# mem.net
KiCad netlist of a schematic drawn in Altium Designer
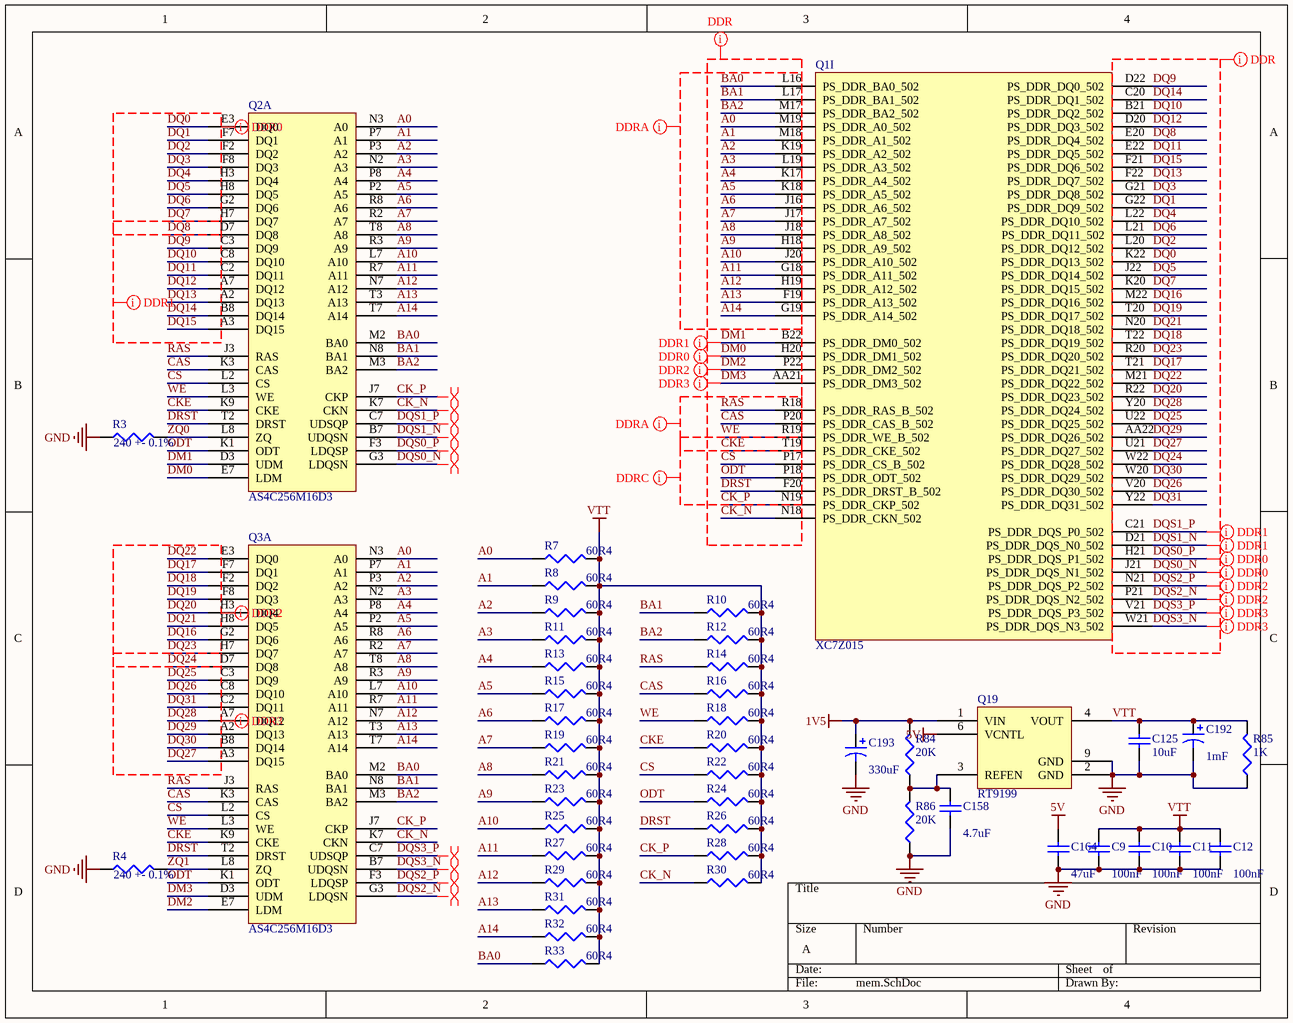
[diagram p0: mem.SchDoc]

(export (version "E")
  (design (tool "Eeschema 10.0.6"))
  (components
    (comp (ref "C9")
      (value "100nF")
      (footprint "CAPC1005X06L")
      (description "Capacitor")
      (fields (field (name "Comment") "Cap") (field (name "PUBLISHER") "Altium Limited"))
      (libsource (lib "Miscellaneous Devices") (part "Cap"))
    )
    (comp (ref "C10")
      (value "100nF")
      (footprint "CAPC1005X06L")
      (description "Capacitor")
      (fields (field (name "Comment") "Cap") (field (name "PUBLISHER") "Altium Limited"))
      (libsource (lib "Miscellaneous Devices") (part "Cap"))
    )
    (comp (ref "C11")
      (value "100nF")
      (footprint "CAPC1005X06L")
      (description "Capacitor")
      (fields (field (name "Comment") "Cap") (field (name "PUBLISHER") "Altium Limited"))
      (libsource (lib "Miscellaneous Devices") (part "Cap"))
    )
    (comp (ref "C12")
      (value "100nF")
      (footprint "CAPC1005X06L")
      (description "Capacitor")
      (fields (field (name "Comment") "Cap") (field (name "PUBLISHER") "Altium Limited"))
      (libsource (lib "Miscellaneous Devices") (part "Cap"))
    )
    (comp (ref "C125")
      (value "10uF")
      (footprint "CAPC1608X90N")
      (description "Capacitor")
      (fields (field (name "Comment") "GRM188R60G106ME47") (field (name "PUBLISHER") "Altium Limited"))
      (libsource (lib "Miscellaneous Devices") (part "Cap"))
    )
    (comp (ref "C158")
      (value "4.7uF")
      (footprint "CAPC1608X90N")
      (description "Capacitor")
      (fields (field (name "Comment") "GRM188R60J475ME19D") (field (name "PUBLISHER") "Altium Limited"))
      (libsource (lib "Miscellaneous Devices") (part "Cap"))
    )
    (comp (ref "C164")
      (value "47uF")
      (footprint "CAPC3225X220N")
      (description "Capacitor")
      (fields (field (name "Comment") "GRM31CR60J476ME19L") (field (name "PUBLISHER") "Altium Limited"))
      (libsource (lib "Miscellaneous Devices") (part "Cap"))
    )
    (comp (ref "C192")
      (value "1mF")
      (footprint "CAP-D/7343-31")
      (description "Polarized Capacitor (Radial)")
      (fields (field (name "Comment") "TR3E108M004C0100") (field (name "PUBLISHER") "Altium Limited"))
      (libsource (lib "Miscellaneous Devices") (part "Cap Pol1"))
    )
    (comp (ref "C193")
      (value "330uF")
      (footprint "CAP-D/7343-31")
      (description "Polarized Capacitor (Radial)")
      (fields (field (name "Comment") "T520D337M006ATE018") (field (name "PUBLISHER") "Altium Limited"))
      (libsource (lib "Miscellaneous Devices") (part "Cap Pol1"))
    )
    (comp (ref "Q1") (value "XC7Z015") (footprint "BGA484x22") (libsource (lib "schlib") (part "XC7Z015")))
    (comp (ref "Q2")
      (value "AS4C256M16D3")
      (footprint "DDR3")
      (libsource (lib "schlib") (part "AS4C256M16D3"))
    )
    (comp (ref "Q3")
      (value "AS4C256M16D3")
      (footprint "DDR3")
      (libsource (lib "schlib") (part "AS4C256M16D3"))
    )
    (comp (ref "Q19")
      (value "RT9199")
      (footprint "SOIC127P600X135_HS-9N")
      (libsource (lib "schlib") (part "RT9199"))
    )
    (comp (ref "R3")
      (value "240 +- 0.1%")
      (footprint "J1-0603")
      (description "Resistor")
      (fields (field (name "Comment") "RG1608P-241-B-T5") (field (name "PUBLISHER") "Altium Limited"))
      (libsource (lib "Miscellaneous Devices") (part "Res3"))
    )
    (comp (ref "R4")
      (value "240 +- 0.1%")
      (footprint "J1-0603")
      (description "Resistor")
      (fields (field (name "Comment") "RG1608P-241-B-T5") (field (name "PUBLISHER") "Altium Limited"))
      (libsource (lib "Miscellaneous Devices") (part "Res3"))
    )
    (comp (ref "R7")
      (value "60R4")
      (footprint "CAPC1005X06L")
      (description "Resistor")
      (fields (field (name "Comment") "RC1005F60R4CS") (field (name "PUBLISHER") "Altium Limited"))
      (libsource (lib "Miscellaneous Devices") (part "Res3"))
    )
    (comp (ref "R8")
      (value "60R4")
      (footprint "CAPC1005X06L")
      (description "Resistor")
      (fields (field (name "Comment") "RC1005F60R4CS") (field (name "PUBLISHER") "Altium Limited"))
      (libsource (lib "Miscellaneous Devices") (part "Res3"))
    )
    (comp (ref "R9")
      (value "60R4")
      (footprint "CAPC1005X06L")
      (description "Resistor")
      (fields (field (name "Comment") "RC1005F60R4CS") (field (name "PUBLISHER") "Altium Limited"))
      (libsource (lib "Miscellaneous Devices") (part "Res3"))
    )
    (comp (ref "R10")
      (value "60R4")
      (footprint "CAPC1005X06L")
      (description "Resistor")
      (fields (field (name "Comment") "RC1005F60R4CS") (field (name "PUBLISHER") "Altium Limited"))
      (libsource (lib "Miscellaneous Devices") (part "Res3"))
    )
    (comp (ref "R11")
      (value "60R4")
      (footprint "CAPC1005X06L")
      (description "Resistor")
      (fields (field (name "Comment") "RC1005F60R4CS") (field (name "PUBLISHER") "Altium Limited"))
      (libsource (lib "Miscellaneous Devices") (part "Res3"))
    )
    (comp (ref "R12")
      (value "60R4")
      (footprint "CAPC1005X06L")
      (description "Resistor")
      (fields (field (name "Comment") "RC1005F60R4CS") (field (name "PUBLISHER") "Altium Limited"))
      (libsource (lib "Miscellaneous Devices") (part "Res3"))
    )
    (comp (ref "R13")
      (value "60R4")
      (footprint "CAPC1005X06L")
      (description "Resistor")
      (fields (field (name "Comment") "RC1005F60R4CS") (field (name "PUBLISHER") "Altium Limited"))
      (libsource (lib "Miscellaneous Devices") (part "Res3"))
    )
    (comp (ref "R14")
      (value "60R4")
      (footprint "CAPC1005X06L")
      (description "Resistor")
      (fields (field (name "Comment") "RC1005F60R4CS") (field (name "PUBLISHER") "Altium Limited"))
      (libsource (lib "Miscellaneous Devices") (part "Res3"))
    )
    (comp (ref "R15")
      (value "60R4")
      (footprint "CAPC1005X06L")
      (description "Resistor")
      (fields (field (name "Comment") "RC1005F60R4CS") (field (name "PUBLISHER") "Altium Limited"))
      (libsource (lib "Miscellaneous Devices") (part "Res3"))
    )
    (comp (ref "R16")
      (value "60R4")
      (footprint "CAPC1005X06L")
      (description "Resistor")
      (fields (field (name "Comment") "RC1005F60R4CS") (field (name "PUBLISHER") "Altium Limited"))
      (libsource (lib "Miscellaneous Devices") (part "Res3"))
    )
    (comp (ref "R17")
      (value "60R4")
      (footprint "CAPC1005X06L")
      (description "Resistor")
      (fields (field (name "Comment") "RC1005F60R4CS") (field (name "PUBLISHER") "Altium Limited"))
      (libsource (lib "Miscellaneous Devices") (part "Res3"))
    )
    (comp (ref "R18")
      (value "60R4")
      (footprint "CAPC1005X06L")
      (description "Resistor")
      (fields (field (name "Comment") "RC1005F60R4CS") (field (name "PUBLISHER") "Altium Limited"))
      (libsource (lib "Miscellaneous Devices") (part "Res3"))
    )
    (comp (ref "R19")
      (value "60R4")
      (footprint "CAPC1005X06L")
      (description "Resistor")
      (fields (field (name "Comment") "RC1005F60R4CS") (field (name "PUBLISHER") "Altium Limited"))
      (libsource (lib "Miscellaneous Devices") (part "Res3"))
    )
    (comp (ref "R20")
      (value "60R4")
      (footprint "CAPC1005X06L")
      (description "Resistor")
      (fields (field (name "Comment") "RC1005F60R4CS") (field (name "PUBLISHER") "Altium Limited"))
      (libsource (lib "Miscellaneous Devices") (part "Res3"))
    )
    (comp (ref "R21")
      (value "60R4")
      (footprint "CAPC1005X06L")
      (description "Resistor")
      (fields (field (name "Comment") "RC1005F60R4CS") (field (name "PUBLISHER") "Altium Limited"))
      (libsource (lib "Miscellaneous Devices") (part "Res3"))
    )
    (comp (ref "R22")
      (value "60R4")
      (footprint "CAPC1005X06L")
      (description "Resistor")
      (fields (field (name "Comment") "RC1005F60R4CS") (field (name "PUBLISHER") "Altium Limited"))
      (libsource (lib "Miscellaneous Devices") (part "Res3"))
    )
    (comp (ref "R23")
      (value "60R4")
      (footprint "CAPC1005X06L")
      (description "Resistor")
      (fields (field (name "Comment") "RC1005F60R4CS") (field (name "PUBLISHER") "Altium Limited"))
      (libsource (lib "Miscellaneous Devices") (part "Res3"))
    )
    (comp (ref "R24")
      (value "60R4")
      (footprint "CAPC1005X06L")
      (description "Resistor")
      (fields (field (name "Comment") "RC1005F60R4CS") (field (name "PUBLISHER") "Altium Limited"))
      (libsource (lib "Miscellaneous Devices") (part "Res3"))
    )
    (comp (ref "R25")
      (value "60R4")
      (footprint "CAPC1005X06L")
      (description "Resistor")
      (fields (field (name "Comment") "RC1005F60R4CS") (field (name "PUBLISHER") "Altium Limited"))
      (libsource (lib "Miscellaneous Devices") (part "Res3"))
    )
    (comp (ref "R26")
      (value "60R4")
      (footprint "CAPC1005X06L")
      (description "Resistor")
      (fields (field (name "Comment") "RC1005F60R4CS") (field (name "PUBLISHER") "Altium Limited"))
      (libsource (lib "Miscellaneous Devices") (part "Res3"))
    )
    (comp (ref "R27")
      (value "60R4")
      (footprint "CAPC1005X06L")
      (description "Resistor")
      (fields (field (name "Comment") "RC1005F60R4CS") (field (name "PUBLISHER") "Altium Limited"))
      (libsource (lib "Miscellaneous Devices") (part "Res3"))
    )
    (comp (ref "R28")
      (value "60R4")
      (footprint "CAPC1005X06L")
      (description "Resistor")
      (fields (field (name "Comment") "RC1005F60R4CS") (field (name "PUBLISHER") "Altium Limited"))
      (libsource (lib "Miscellaneous Devices") (part "Res3"))
    )
    (comp (ref "R29")
      (value "60R4")
      (footprint "CAPC1005X06L")
      (description "Resistor")
      (fields (field (name "Comment") "RC1005F60R4CS") (field (name "PUBLISHER") "Altium Limited"))
      (libsource (lib "Miscellaneous Devices") (part "Res3"))
    )
    (comp (ref "R30")
      (value "60R4")
      (footprint "CAPC1005X06L")
      (description "Resistor")
      (fields (field (name "Comment") "RC1005F60R4CS") (field (name "PUBLISHER") "Altium Limited"))
      (libsource (lib "Miscellaneous Devices") (part "Res3"))
    )
    (comp (ref "R31")
      (value "60R4")
      (footprint "CAPC1005X06L")
      (description "Resistor")
      (fields (field (name "Comment") "RC1005F60R4CS") (field (name "PUBLISHER") "Altium Limited"))
      (libsource (lib "Miscellaneous Devices") (part "Res3"))
    )
    (comp (ref "R32")
      (value "60R4")
      (footprint "CAPC1005X06L")
      (description "Resistor")
      (fields (field (name "Comment") "RC1005F60R4CS") (field (name "PUBLISHER") "Altium Limited"))
      (libsource (lib "Miscellaneous Devices") (part "Res3"))
    )
    (comp (ref "R33")
      (value "60R4")
      (footprint "CAPC1005X06L")
      (description "Resistor")
      (fields (field (name "Comment") "RC1005F60R4CS") (field (name "PUBLISHER") "Altium Limited"))
      (libsource (lib "Miscellaneous Devices") (part "Res3"))
    )
    (comp (ref "R84")
      (value "20K")
      (footprint "J1-0603")
      (description "Resistor")
      (fields (field (name "Comment") "RC1608F203CS") (field (name "PUBLISHER") "Altium Limited"))
      (libsource (lib "Miscellaneous Devices") (part "Res3"))
    )
    (comp (ref "R85")
      (value "1K")
      (footprint "J1-0603")
      (description "Resistor")
      (fields (field (name "Comment") "RC1608J102CS") (field (name "PUBLISHER") "Altium Limited"))
      (libsource (lib "Miscellaneous Devices") (part "Res3"))
    )
    (comp (ref "R86")
      (value "20K")
      (footprint "J1-0603")
      (description "Resistor")
      (fields (field (name "Comment") "RC1608F203CS") (field (name "PUBLISHER") "Altium Limited"))
      (libsource (lib "Miscellaneous Devices") (part "Res3"))
    )
  )
  (nets
    (net (code "1") (name "/A0") (class "Default")
      (node (ref "Q1") (pin "M19") (pinfunction "PS_DDR_A0_502_M19") (pintype "passive"))
      (node (ref "Q2") (pin "N3") (pinfunction "A0_N3") (pintype "passive"))
      (node (ref "Q3") (pin "N3") (pinfunction "A0_N3") (pintype "passive"))
      (node (ref "R7") (pin "1") (pinfunction "1_1") (pintype "passive"))
    )
    (net (code "2") (name "/A1") (class "Default")
      (node (ref "Q1") (pin "M18") (pinfunction "PS_DDR_A1_502_M18") (pintype "passive"))
      (node (ref "Q2") (pin "P7") (pinfunction "A1_P7") (pintype "passive"))
      (node (ref "Q3") (pin "P7") (pinfunction "A1_P7") (pintype "passive"))
      (node (ref "R8") (pin "1") (pinfunction "1_1") (pintype "passive"))
    )
    (net (code "3") (name "/A2") (class "Default")
      (node (ref "Q1") (pin "K19") (pinfunction "PS_DDR_A2_502_K19") (pintype "passive"))
      (node (ref "Q2") (pin "P3") (pinfunction "A2_P3") (pintype "passive"))
      (node (ref "Q3") (pin "P3") (pinfunction "A2_P3") (pintype "passive"))
      (node (ref "R9") (pin "1") (pinfunction "1_1") (pintype "passive"))
    )
    (net (code "4") (name "/A3") (class "Default")
      (node (ref "Q1") (pin "L19") (pinfunction "PS_DDR_A3_502_L19") (pintype "passive"))
      (node (ref "Q2") (pin "N2") (pinfunction "A3_N2") (pintype "passive"))
      (node (ref "Q3") (pin "N2") (pinfunction "A3_N2") (pintype "passive"))
      (node (ref "R11") (pin "1") (pinfunction "1_1") (pintype "passive"))
    )
    (net (code "5") (name "/A4") (class "Default")
      (node (ref "Q1") (pin "K17") (pinfunction "PS_DDR_A4_502_K17") (pintype "passive"))
      (node (ref "Q2") (pin "P8") (pinfunction "A4_P8") (pintype "passive"))
      (node (ref "Q3") (pin "P8") (pinfunction "A4_P8") (pintype "passive"))
      (node (ref "R13") (pin "1") (pinfunction "1_1") (pintype "passive"))
    )
    (net (code "6") (name "/A5") (class "Default")
      (node (ref "Q1") (pin "K18") (pinfunction "PS_DDR_A5_502_K18") (pintype "passive"))
      (node (ref "Q2") (pin "P2") (pinfunction "A5_P2") (pintype "passive"))
      (node (ref "Q3") (pin "P2") (pinfunction "A5_P2") (pintype "passive"))
      (node (ref "R15") (pin "1") (pinfunction "1_1") (pintype "passive"))
    )
    (net (code "7") (name "/A6") (class "Default")
      (node (ref "Q1") (pin "J16") (pinfunction "PS_DDR_A6_502_J16") (pintype "passive"))
      (node (ref "Q2") (pin "R8") (pinfunction "A6_R8") (pintype "passive"))
      (node (ref "Q3") (pin "R8") (pinfunction "A6_R8") (pintype "passive"))
      (node (ref "R17") (pin "1") (pinfunction "1_1") (pintype "passive"))
    )
    (net (code "8") (name "/A7") (class "Default")
      (node (ref "Q1") (pin "J17") (pinfunction "PS_DDR_A7_502_J17") (pintype "passive"))
      (node (ref "Q2") (pin "R2") (pinfunction "A7_R2") (pintype "passive"))
      (node (ref "Q3") (pin "R2") (pinfunction "A7_R2") (pintype "passive"))
      (node (ref "R19") (pin "1") (pinfunction "1_1") (pintype "passive"))
    )
    (net (code "9") (name "/A8") (class "Default")
      (node (ref "Q1") (pin "J18") (pinfunction "PS_DDR_A8_502_J18") (pintype "passive"))
      (node (ref "Q2") (pin "T8") (pinfunction "A8_T8") (pintype "passive"))
      (node (ref "Q3") (pin "T8") (pinfunction "A8_T8") (pintype "passive"))
      (node (ref "R21") (pin "1") (pinfunction "1_1") (pintype "passive"))
    )
    (net (code "10") (name "/A9") (class "Default")
      (node (ref "Q1") (pin "H18") (pinfunction "PS_DDR_A9_502_H18") (pintype "passive"))
      (node (ref "Q2") (pin "R3") (pinfunction "A9_R3") (pintype "passive"))
      (node (ref "Q3") (pin "R3") (pinfunction "A9_R3") (pintype "passive"))
      (node (ref "R23") (pin "1") (pinfunction "1_1") (pintype "passive"))
    )
    (net (code "11") (name "/A10") (class "Default")
      (node (ref "Q1") (pin "J20") (pinfunction "PS_DDR_A10_502_J20") (pintype "passive"))
      (node (ref "Q2") (pin "L7") (pinfunction "A10_L7") (pintype "passive"))
      (node (ref "Q3") (pin "L7") (pinfunction "A10_L7") (pintype "passive"))
      (node (ref "R25") (pin "1") (pinfunction "1_1") (pintype "passive"))
    )
    (net (code "12") (name "/A11") (class "Default")
      (node (ref "Q1") (pin "G18") (pinfunction "PS_DDR_A11_502_G18") (pintype "passive"))
      (node (ref "Q2") (pin "R7") (pinfunction "A11_R7") (pintype "passive"))
      (node (ref "Q3") (pin "R7") (pinfunction "A11_R7") (pintype "passive"))
      (node (ref "R27") (pin "1") (pinfunction "1_1") (pintype "passive"))
    )
    (net (code "13") (name "/A12") (class "Default")
      (node (ref "Q1") (pin "H19") (pinfunction "PS_DDR_A12_502_H19") (pintype "passive"))
      (node (ref "Q2") (pin "N7") (pinfunction "A12_N7") (pintype "passive"))
      (node (ref "Q3") (pin "N7") (pinfunction "A12_N7") (pintype "passive"))
      (node (ref "R29") (pin "1") (pinfunction "1_1") (pintype "passive"))
    )
    (net (code "14") (name "/A13") (class "Default")
      (node (ref "Q1") (pin "F19") (pinfunction "PS_DDR_A13_502_F19") (pintype "passive"))
      (node (ref "Q2") (pin "T3") (pinfunction "A13_T3") (pintype "passive"))
      (node (ref "Q3") (pin "T3") (pinfunction "A13_T3") (pintype "passive"))
      (node (ref "R31") (pin "1") (pinfunction "1_1") (pintype "passive"))
    )
    (net (code "15") (name "/A14") (class "Default")
      (node (ref "Q1") (pin "G19") (pinfunction "PS_DDR_A14_502_G19") (pintype "passive"))
      (node (ref "Q2") (pin "T7") (pinfunction "A14_T7") (pintype "passive"))
      (node (ref "Q3") (pin "T7") (pinfunction "A14_T7") (pintype "passive"))
      (node (ref "R32") (pin "1") (pinfunction "1_1") (pintype "passive"))
    )
    (net (code "16") (name "/BA0") (class "Default")
      (node (ref "Q1") (pin "L16") (pinfunction "PS_DDR_BA0_502_L16") (pintype "passive"))
      (node (ref "Q2") (pin "M2") (pinfunction "BA0_M2") (pintype "passive"))
      (node (ref "Q3") (pin "M2") (pinfunction "BA0_M2") (pintype "passive"))
      (node (ref "R33") (pin "1") (pinfunction "1_1") (pintype "passive"))
    )
    (net (code "17") (name "/BA1") (class "Default")
      (node (ref "Q1") (pin "L17") (pinfunction "PS_DDR_BA1_502_L17") (pintype "passive"))
      (node (ref "Q2") (pin "N8") (pinfunction "BA1_N8") (pintype "passive"))
      (node (ref "Q3") (pin "N8") (pinfunction "BA1_N8") (pintype "passive"))
      (node (ref "R10") (pin "1") (pinfunction "1_1") (pintype "passive"))
    )
    (net (code "18") (name "/BA2") (class "Default")
      (node (ref "Q1") (pin "M17") (pinfunction "PS_DDR_BA2_502_M17") (pintype "passive"))
      (node (ref "Q2") (pin "M3") (pinfunction "BA2_M3") (pintype "passive"))
      (node (ref "Q3") (pin "M3") (pinfunction "BA2_M3") (pintype "passive"))
      (node (ref "R12") (pin "1") (pinfunction "1_1") (pintype "passive"))
    )
    (net (code "19") (name "/CAS") (class "Default")
      (node (ref "Q1") (pin "P20") (pinfunction "PS_DDR_CAS_B_502_P20") (pintype "passive"))
      (node (ref "Q2") (pin "K3") (pinfunction "CAS_K3") (pintype "passive"))
      (node (ref "Q3") (pin "K3") (pinfunction "CAS_K3") (pintype "passive"))
      (node (ref "R16") (pin "1") (pinfunction "1_1") (pintype "passive"))
    )
    (net (code "20") (name "/CKE") (class "Default")
      (node (ref "Q1") (pin "T19") (pinfunction "PS_DDR_CKE_502_T19") (pintype "passive"))
      (node (ref "Q2") (pin "K9") (pinfunction "CKE_K9") (pintype "passive"))
      (node (ref "Q3") (pin "K9") (pinfunction "CKE_K9") (pintype "passive"))
      (node (ref "R20") (pin "1") (pinfunction "1_1") (pintype "passive"))
    )
    (net (code "21") (name "/CK_N") (class "Default")
      (node (ref "Q1") (pin "N18") (pinfunction "PS_DDR_CKN_502_N18") (pintype "passive"))
      (node (ref "Q2") (pin "K7") (pinfunction "CKN_K7") (pintype "passive"))
      (node (ref "Q3") (pin "K7") (pinfunction "CKN_K7") (pintype "passive"))
      (node (ref "R30") (pin "1") (pinfunction "1_1") (pintype "passive"))
    )
    (net (code "22") (name "/CK_P") (class "Default")
      (node (ref "Q1") (pin "N19") (pinfunction "PS_DDR_CKP_502_N19") (pintype "passive"))
      (node (ref "Q2") (pin "J7") (pinfunction "CKP_J7") (pintype "passive"))
      (node (ref "Q3") (pin "J7") (pinfunction "CKP_J7") (pintype "passive"))
      (node (ref "R28") (pin "1") (pinfunction "1_1") (pintype "passive"))
    )
    (net (code "23") (name "/CS") (class "Default")
      (node (ref "Q1") (pin "P17") (pinfunction "PS_DDR_CS_B_502_P17") (pintype "passive"))
      (node (ref "Q2") (pin "L2") (pinfunction "CS_L2") (pintype "passive"))
      (node (ref "Q3") (pin "L2") (pinfunction "CS_L2") (pintype "passive"))
      (node (ref "R22") (pin "1") (pinfunction "1_1") (pintype "passive"))
    )
    (net (code "24") (name "/DM0") (class "Default")
      (node (ref "Q1") (pin "H20") (pinfunction "PS_DDR_DM1_502_H20") (pintype "passive"))
      (node (ref "Q2") (pin "E7") (pinfunction "LDM_E7") (pintype "passive"))
    )
    (net (code "25") (name "/DM1") (class "Default")
      (node (ref "Q1") (pin "B22") (pinfunction "PS_DDR_DM0_502_B22") (pintype "passive"))
      (node (ref "Q2") (pin "D3") (pinfunction "UDM_D3") (pintype "passive"))
    )
    (net (code "26") (name "/DM2") (class "Default")
      (node (ref "Q1") (pin "P22") (pinfunction "PS_DDR_DM2_502_P22") (pintype "passive"))
      (node (ref "Q3") (pin "E7") (pinfunction "LDM_E7") (pintype "passive"))
    )
    (net (code "27") (name "/DM3") (class "Default")
      (node (ref "Q1") (pin "AA21") (pinfunction "PS_DDR_DM3_502_AA21") (pintype "passive"))
      (node (ref "Q3") (pin "D3") (pinfunction "UDM_D3") (pintype "passive"))
    )
    (net (code "28") (name "/DQ0") (class "Default")
      (node (ref "Q1") (pin "K22") (pinfunction "PS_DDR_DQ13_502_K22") (pintype "passive"))
      (node (ref "Q2") (pin "E3") (pinfunction "DQ0_E3") (pintype "passive"))
    )
    (net (code "29") (name "/DQ1") (class "Default")
      (node (ref "Q1") (pin "G22") (pinfunction "PS_DDR_DQ9_502_G22") (pintype "passive"))
      (node (ref "Q2") (pin "F7") (pinfunction "DQ1_F7") (pintype "passive"))
    )
    (net (code "30") (name "/DQ2") (class "Default")
      (node (ref "Q1") (pin "L20") (pinfunction "PS_DDR_DQ12_502_L20") (pintype "passive"))
      (node (ref "Q2") (pin "F2") (pinfunction "DQ2_F2") (pintype "passive"))
    )
    (net (code "31") (name "/DQ3") (class "Default")
      (node (ref "Q1") (pin "G21") (pinfunction "PS_DDR_DQ8_502_G21") (pintype "passive"))
      (node (ref "Q2") (pin "F8") (pinfunction "DQ3_F8") (pintype "passive"))
    )
    (net (code "32") (name "/DQ4") (class "Default")
      (node (ref "Q1") (pin "L22") (pinfunction "PS_DDR_DQ10_502_L22") (pintype "passive"))
      (node (ref "Q2") (pin "H3") (pinfunction "DQ4_H3") (pintype "passive"))
    )
    (net (code "33") (name "/DQ5") (class "Default")
      (node (ref "Q1") (pin "J22") (pinfunction "PS_DDR_DQ14_502_J22") (pintype "passive"))
      (node (ref "Q2") (pin "H8") (pinfunction "DQ5_H8") (pintype "passive"))
    )
    (net (code "34") (name "/DQ6") (class "Default")
      (node (ref "Q1") (pin "L21") (pinfunction "PS_DDR_DQ11_502_L21") (pintype "passive"))
      (node (ref "Q2") (pin "G2") (pinfunction "DQ6_G2") (pintype "passive"))
    )
    (net (code "35") (name "/DQ7") (class "Default")
      (node (ref "Q1") (pin "K20") (pinfunction "PS_DDR_DQ15_502_K20") (pintype "passive"))
      (node (ref "Q2") (pin "H7") (pinfunction "DQ7_H7") (pintype "passive"))
    )
    (net (code "36") (name "/DQ8") (class "Default")
      (node (ref "Q1") (pin "E20") (pinfunction "PS_DDR_DQ4_502_E20") (pintype "passive"))
      (node (ref "Q2") (pin "D7") (pinfunction "DQ8_D7") (pintype "passive"))
    )
    (net (code "37") (name "/DQ9") (class "Default")
      (node (ref "Q1") (pin "D22") (pinfunction "PS_DDR_DQ0_502_D22") (pintype "passive"))
      (node (ref "Q2") (pin "C3") (pinfunction "DQ9_C3") (pintype "passive"))
    )
    (net (code "38") (name "/DQ10") (class "Default")
      (node (ref "Q1") (pin "B21") (pinfunction "PS_DDR_DQ2_502_B21") (pintype "passive"))
      (node (ref "Q2") (pin "C8") (pinfunction "DQ10_C8") (pintype "passive"))
    )
    (net (code "39") (name "/DQ11") (class "Default")
      (node (ref "Q1") (pin "E22") (pinfunction "PS_DDR_DQ5_502_E22") (pintype "passive"))
      (node (ref "Q2") (pin "C2") (pinfunction "DQ11_C2") (pintype "passive"))
    )
    (net (code "40") (name "/DQ12") (class "Default")
      (node (ref "Q1") (pin "D20") (pinfunction "PS_DDR_DQ3_502_D20") (pintype "passive"))
      (node (ref "Q2") (pin "A7") (pinfunction "DQ12_A7") (pintype "passive"))
    )
    (net (code "41") (name "/DQ13") (class "Default")
      (node (ref "Q1") (pin "F22") (pinfunction "PS_DDR_DQ7_502_F22") (pintype "passive"))
      (node (ref "Q2") (pin "A2") (pinfunction "DQ13_A2") (pintype "passive"))
    )
    (net (code "42") (name "/DQ14") (class "Default")
      (node (ref "Q1") (pin "C20") (pinfunction "PS_DDR_DQ1_502_C20") (pintype "passive"))
      (node (ref "Q2") (pin "B8") (pinfunction "DQ14_B8") (pintype "passive"))
    )
    (net (code "43") (name "/DQ15") (class "Default")
      (node (ref "Q1") (pin "F21") (pinfunction "PS_DDR_DQ6_502_F21") (pintype "passive"))
      (node (ref "Q2") (pin "A3") (pinfunction "DQ15_A3") (pintype "passive"))
    )
    (net (code "44") (name "/DQ16") (class "Default")
      (node (ref "Q1") (pin "M22") (pinfunction "PS_DDR_DQ16_502_M22") (pintype "passive"))
      (node (ref "Q3") (pin "G2") (pinfunction "DQ6_G2") (pintype "passive"))
    )
    (net (code "45") (name "/DQ17") (class "Default")
      (node (ref "Q1") (pin "T21") (pinfunction "PS_DDR_DQ21_502_T21") (pintype "passive"))
      (node (ref "Q3") (pin "F7") (pinfunction "DQ1_F7") (pintype "passive"))
    )
    (net (code "46") (name "/DQ18") (class "Default")
      (node (ref "Q1") (pin "T22") (pinfunction "PS_DDR_DQ19_502_T22") (pintype "passive"))
      (node (ref "Q3") (pin "F2") (pinfunction "DQ2_F2") (pintype "passive"))
    )
    (net (code "47") (name "/DQ19") (class "Default")
      (node (ref "Q1") (pin "T20") (pinfunction "PS_DDR_DQ17_502_T20") (pintype "passive"))
      (node (ref "Q3") (pin "F8") (pinfunction "DQ3_F8") (pintype "passive"))
    )
    (net (code "48") (name "/DQ20") (class "Default")
      (node (ref "Q1") (pin "R22") (pinfunction "PS_DDR_DQ23_502_R22") (pintype "passive"))
      (node (ref "Q3") (pin "H3") (pinfunction "DQ4_H3") (pintype "passive"))
    )
    (net (code "49") (name "/DQ21") (class "Default")
      (node (ref "Q1") (pin "N20") (pinfunction "PS_DDR_DQ18_502_N20") (pintype "passive"))
      (node (ref "Q3") (pin "H8") (pinfunction "DQ5_H8") (pintype "passive"))
    )
    (net (code "50") (name "/DQ22") (class "Default")
      (node (ref "Q1") (pin "M21") (pinfunction "PS_DDR_DQ22_502_M21") (pintype "passive"))
      (node (ref "Q3") (pin "E3") (pinfunction "DQ0_E3") (pintype "passive"))
    )
    (net (code "51") (name "/DQ23") (class "Default")
      (node (ref "Q1") (pin "R20") (pinfunction "PS_DDR_DQ20_502_R20") (pintype "passive"))
      (node (ref "Q3") (pin "H7") (pinfunction "DQ7_H7") (pintype "passive"))
    )
    (net (code "52") (name "/DQ24") (class "Default")
      (node (ref "Q1") (pin "W22") (pinfunction "PS_DDR_DQ28_502_W22") (pintype "passive"))
      (node (ref "Q3") (pin "D7") (pinfunction "DQ8_D7") (pintype "passive"))
    )
    (net (code "53") (name "/DQ25") (class "Default")
      (node (ref "Q1") (pin "U22") (pinfunction "PS_DDR_DQ25_502_U22") (pintype "passive"))
      (node (ref "Q3") (pin "C3") (pinfunction "DQ9_C3") (pintype "passive"))
    )
    (net (code "54") (name "/DQ26") (class "Default")
      (node (ref "Q1") (pin "V20") (pinfunction "PS_DDR_DQ30_502_V20") (pintype "passive"))
      (node (ref "Q3") (pin "C8") (pinfunction "DQ10_C8") (pintype "passive"))
    )
    (net (code "55") (name "/DQ27") (class "Default")
      (node (ref "Q1") (pin "U21") (pinfunction "PS_DDR_DQ27_502_U21") (pintype "passive"))
      (node (ref "Q3") (pin "A3") (pinfunction "DQ15_A3") (pintype "passive"))
    )
    (net (code "56") (name "/DQ28") (class "Default")
      (node (ref "Q1") (pin "Y20") (pinfunction "PS_DDR_DQ24_502_Y20") (pintype "passive"))
      (node (ref "Q3") (pin "A7") (pinfunction "DQ12_A7") (pintype "passive"))
    )
    (net (code "57") (name "/DQ29") (class "Default")
      (node (ref "Q1") (pin "AA22") (pinfunction "PS_DDR_DQ26_502_AA22") (pintype "passive"))
      (node (ref "Q3") (pin "A2") (pinfunction "DQ13_A2") (pintype "passive"))
    )
    (net (code "58") (name "/DQ30") (class "Default")
      (node (ref "Q1") (pin "W20") (pinfunction "PS_DDR_DQ29_502_W20") (pintype "passive"))
      (node (ref "Q3") (pin "B8") (pinfunction "DQ14_B8") (pintype "passive"))
    )
    (net (code "59") (name "/DQ31") (class "Default")
      (node (ref "Q1") (pin "Y22") (pinfunction "PS_DDR_DQ31_502_Y22") (pintype "passive"))
      (node (ref "Q3") (pin "C2") (pinfunction "DQ11_C2") (pintype "passive"))
    )
    (net (code "60") (name "/DQS0_N") (class "Default")
      (node (ref "Q1") (pin "J21") (pinfunction "PS_DDR_DQS_N1_502_J21") (pintype "passive"))
      (node (ref "Q2") (pin "G3") (pinfunction "LDQSN_G3") (pintype "passive"))
    )
    (net (code "61") (name "/DQS0_P") (class "Default")
      (node (ref "Q1") (pin "H21") (pinfunction "PS_DDR_DQS_P1_502_H21") (pintype "passive"))
      (node (ref "Q2") (pin "F3") (pinfunction "LDQSP_F3") (pintype "passive"))
    )
    (net (code "62") (name "/DQS1_N") (class "Default")
      (node (ref "Q1") (pin "D21") (pinfunction "PS_DDR_DQS_N0_502_D21") (pintype "passive"))
      (node (ref "Q2") (pin "B7") (pinfunction "UDQSN_B7") (pintype "passive"))
    )
    (net (code "63") (name "/DQS1_P") (class "Default")
      (node (ref "Q1") (pin "C21") (pinfunction "PS_DDR_DQS_P0_502_C21") (pintype "passive"))
      (node (ref "Q2") (pin "C7") (pinfunction "UDSQP_C7") (pintype "passive"))
    )
    (net (code "64") (name "/DQS2_N") (class "Default")
      (node (ref "Q1") (pin "P21") (pinfunction "PS_DDR_DQS_N2_502_P21") (pintype "passive"))
      (node (ref "Q3") (pin "G3") (pinfunction "LDQSN_G3") (pintype "passive"))
    )
    (net (code "65") (name "/DQS2_P") (class "Default")
      (node (ref "Q1") (pin "N21") (pinfunction "PS_DDR_DQS_P2_502_N21") (pintype "passive"))
      (node (ref "Q3") (pin "F3") (pinfunction "LDQSP_F3") (pintype "passive"))
    )
    (net (code "66") (name "/DQS3_N") (class "Default")
      (node (ref "Q1") (pin "W21") (pinfunction "PS_DDR_DQS_N3_502_W21") (pintype "passive"))
      (node (ref "Q3") (pin "B7") (pinfunction "UDQSN_B7") (pintype "passive"))
    )
    (net (code "67") (name "/DQS3_P") (class "Default")
      (node (ref "Q1") (pin "V21") (pinfunction "PS_DDR_DQS_P3_502_V21") (pintype "passive"))
      (node (ref "Q3") (pin "C7") (pinfunction "UDSQP_C7") (pintype "passive"))
    )
    (net (code "68") (name "/DRST") (class "Default")
      (node (ref "Q1") (pin "F20") (pinfunction "PS_DDR_DRST_B_502_F20") (pintype "passive"))
      (node (ref "Q2") (pin "T2") (pinfunction "DRST_T2") (pintype "passive"))
      (node (ref "Q3") (pin "T2") (pinfunction "DRST_T2") (pintype "passive"))
      (node (ref "R26") (pin "1") (pinfunction "1_1") (pintype "passive"))
    )
    (net (code "69") (name "/ODT") (class "Default")
      (node (ref "Q1") (pin "P18") (pinfunction "PS_DDR_ODT_502_P18") (pintype "passive"))
      (node (ref "Q2") (pin "K1") (pinfunction "ODT_K1") (pintype "passive"))
      (node (ref "Q3") (pin "K1") (pinfunction "ODT_K1") (pintype "passive"))
      (node (ref "R24") (pin "1") (pinfunction "1_1") (pintype "passive"))
    )
    (net (code "70") (name "/RAS") (class "Default")
      (node (ref "Q1") (pin "R18") (pinfunction "PS_DDR_RAS_B_502_R18") (pintype "passive"))
      (node (ref "Q2") (pin "J3") (pinfunction "RAS_J3") (pintype "passive"))
      (node (ref "Q3") (pin "J3") (pinfunction "RAS_J3") (pintype "passive"))
      (node (ref "R14") (pin "1") (pinfunction "1_1") (pintype "passive"))
    )
    (net (code "71") (name "/WE") (class "Default")
      (node (ref "Q1") (pin "R19") (pinfunction "PS_DDR_WE_B_502_R19") (pintype "passive"))
      (node (ref "Q2") (pin "L3") (pinfunction "WE_L3") (pintype "passive"))
      (node (ref "Q3") (pin "L3") (pinfunction "WE_L3") (pintype "passive"))
      (node (ref "R18") (pin "1") (pinfunction "1_1") (pintype "passive"))
    )
    (net (code "72") (name "/ZQ0") (class "Default")
      (node (ref "Q2") (pin "L8") (pinfunction "ZQ_L8") (pintype "passive"))
      (node (ref "R3") (pin "2") (pinfunction "2_2") (pintype "passive"))
    )
    (net (code "73") (name "/ZQ1") (class "Default")
      (node (ref "Q3") (pin "L8") (pinfunction "ZQ_L8") (pintype "passive"))
      (node (ref "R4") (pin "2") (pinfunction "2_2") (pintype "passive"))
    )
    (net (code "74") (name "1V5") (class "Default")
      (node (ref "C193") (pin "1") (pinfunction "1_1") (pintype "passive"))
      (node (ref "Q19") (pin "1") (pinfunction "VIN_1") (pintype "passive"))
      (node (ref "R84") (pin "2") (pinfunction "2_2") (pintype "passive"))
    )
    (net (code "75") (name "5V") (class "Default")
      (node (ref "C164") (pin "2") (pinfunction "2_2") (pintype "passive"))
      (node (ref "Q19") (pin "6") (pinfunction "VCNTL_6") (pintype "passive"))
    )
    (net (code "76") (name "GND") (class "Default")
      (node (ref "C10") (pin "1") (pinfunction "1_1") (pintype "passive"))
      (node (ref "C11") (pin "1") (pinfunction "1_1") (pintype "passive"))
      (node (ref "C12") (pin "1") (pinfunction "1_1") (pintype "passive"))
      (node (ref "C125") (pin "2") (pinfunction "2_2") (pintype "passive"))
      (node (ref "C158") (pin "1") (pinfunction "1_1") (pintype "passive"))
      (node (ref "C164") (pin "1") (pinfunction "1_1") (pintype "passive"))
      (node (ref "C192") (pin "2") (pinfunction "2_2") (pintype "passive"))
      (node (ref "C193") (pin "2") (pinfunction "2_2") (pintype "passive"))
      (node (ref "C9") (pin "1") (pinfunction "1_1") (pintype "passive"))
      (node (ref "Q19") (pin "2") (pinfunction "GND_2") (pintype "passive"))
      (node (ref "Q19") (pin "9") (pinfunction "GND_9") (pintype "passive"))
      (node (ref "R3") (pin "1") (pinfunction "1_1") (pintype "passive"))
      (node (ref "R4") (pin "1") (pinfunction "1_1") (pintype "passive"))
      (node (ref "R85") (pin "1") (pinfunction "1_1") (pintype "passive"))
      (node (ref "R86") (pin "1") (pinfunction "1_1") (pintype "passive"))
    )
    (net (code "77") (name "Net-(Q19-REFEN)") (class "Default")
      (node (ref "C158") (pin "2") (pinfunction "2_2") (pintype "passive"))
      (node (ref "Q19") (pin "3") (pinfunction "REFEN_3") (pintype "passive"))
      (node (ref "R84") (pin "1") (pinfunction "1_1") (pintype "passive"))
      (node (ref "R86") (pin "2") (pinfunction "2_2") (pintype "passive"))
    )
    (net (code "78") (name "VTT") (class "Default")
      (node (ref "C10") (pin "2") (pinfunction "2_2") (pintype "passive"))
      (node (ref "C11") (pin "2") (pinfunction "2_2") (pintype "passive"))
      (node (ref "C12") (pin "2") (pinfunction "2_2") (pintype "passive"))
      (node (ref "C125") (pin "1") (pinfunction "1_1") (pintype "passive"))
      (node (ref "C192") (pin "1") (pinfunction "1_1") (pintype "passive"))
      (node (ref "C9") (pin "2") (pinfunction "2_2") (pintype "passive"))
      (node (ref "Q19") (pin "4") (pinfunction "VOUT_4") (pintype "passive"))
      (node (ref "R10") (pin "2") (pinfunction "2_2") (pintype "passive"))
      (node (ref "R11") (pin "2") (pinfunction "2_2") (pintype "passive"))
      (node (ref "R12") (pin "2") (pinfunction "2_2") (pintype "passive"))
      (node (ref "R13") (pin "2") (pinfunction "2_2") (pintype "passive"))
      (node (ref "R14") (pin "2") (pinfunction "2_2") (pintype "passive"))
      (node (ref "R15") (pin "2") (pinfunction "2_2") (pintype "passive"))
      (node (ref "R16") (pin "2") (pinfunction "2_2") (pintype "passive"))
      (node (ref "R17") (pin "2") (pinfunction "2_2") (pintype "passive"))
      (node (ref "R18") (pin "2") (pinfunction "2_2") (pintype "passive"))
      (node (ref "R19") (pin "2") (pinfunction "2_2") (pintype "passive"))
      (node (ref "R20") (pin "2") (pinfunction "2_2") (pintype "passive"))
      (node (ref "R21") (pin "2") (pinfunction "2_2") (pintype "passive"))
      (node (ref "R22") (pin "2") (pinfunction "2_2") (pintype "passive"))
      (node (ref "R23") (pin "2") (pinfunction "2_2") (pintype "passive"))
      (node (ref "R24") (pin "2") (pinfunction "2_2") (pintype "passive"))
      (node (ref "R25") (pin "2") (pinfunction "2_2") (pintype "passive"))
      (node (ref "R26") (pin "2") (pinfunction "2_2") (pintype "passive"))
      (node (ref "R27") (pin "2") (pinfunction "2_2") (pintype "passive"))
      (node (ref "R28") (pin "2") (pinfunction "2_2") (pintype "passive"))
      (node (ref "R29") (pin "2") (pinfunction "2_2") (pintype "passive"))
      (node (ref "R30") (pin "2") (pinfunction "2_2") (pintype "passive"))
      (node (ref "R31") (pin "2") (pinfunction "2_2") (pintype "passive"))
      (node (ref "R32") (pin "2") (pinfunction "2_2") (pintype "passive"))
      (node (ref "R33") (pin "2") (pinfunction "2_2") (pintype "passive"))
      (node (ref "R7") (pin "2") (pinfunction "2_2") (pintype "passive"))
      (node (ref "R8") (pin "2") (pinfunction "2_2") (pintype "passive"))
      (node (ref "R85") (pin "2") (pinfunction "2_2") (pintype "passive"))
      (node (ref "R9") (pin "2") (pinfunction "2_2") (pintype "passive"))
    )
  )
)
